# Cyusb3014_-_1.net
KiCad netlist of a schematic drawn in Altium Designer
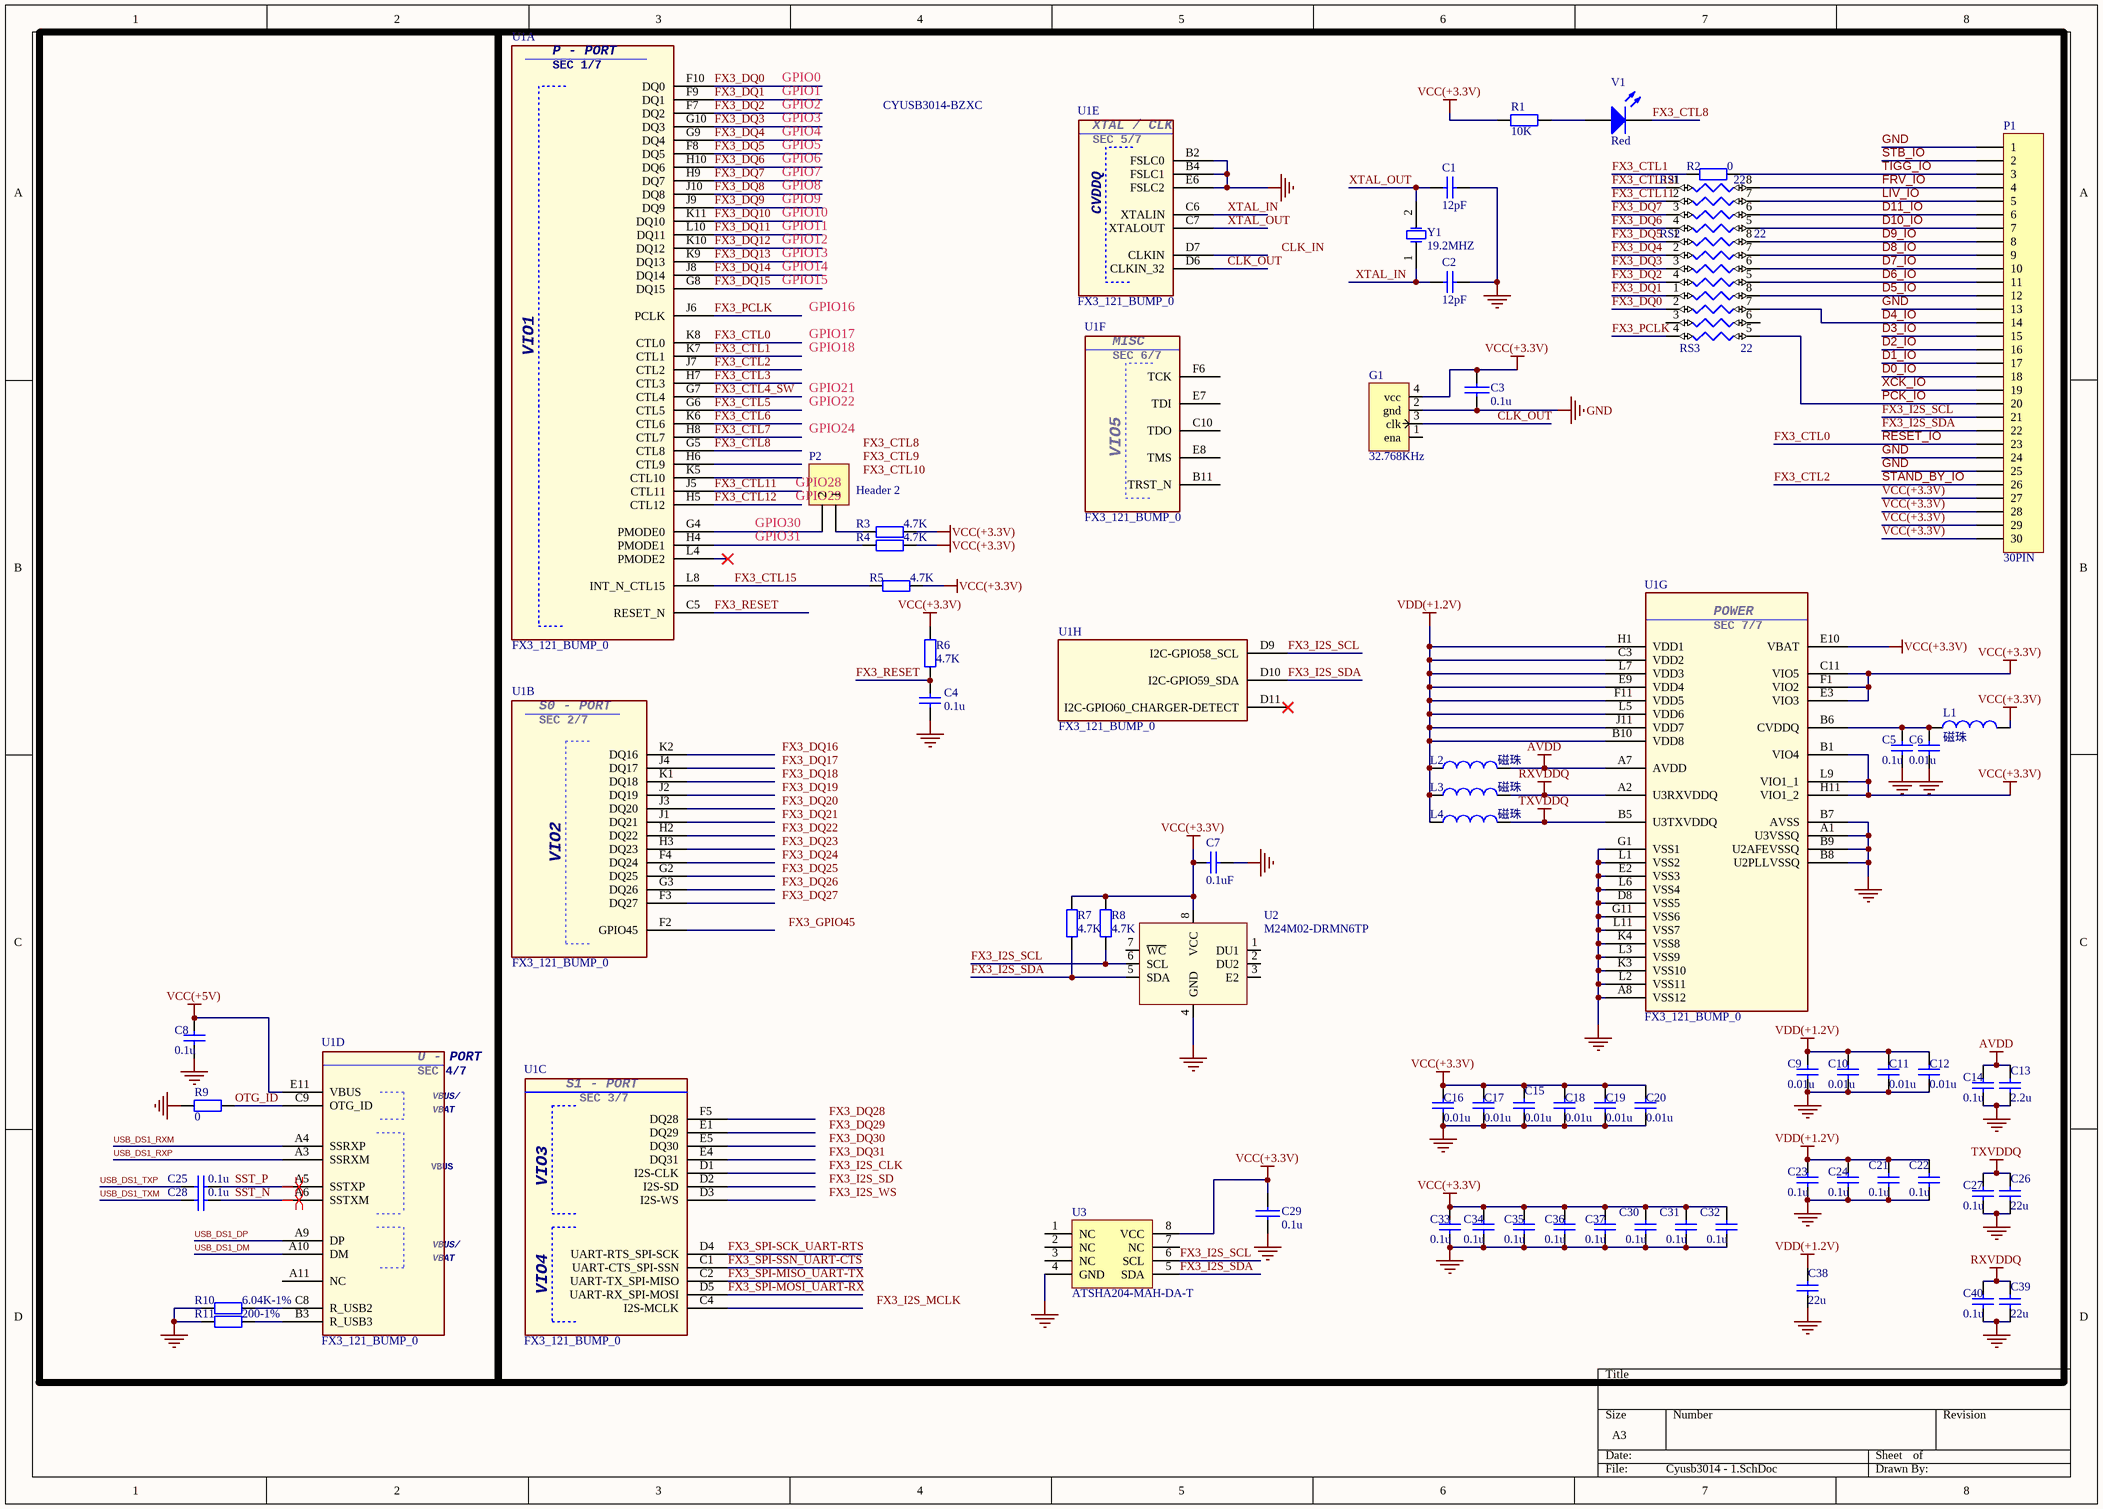
[diagram p0: Cyusb3014 - 1.SchDoc]

(export (version "E")
  (design (tool "Eeschema 10.0.6"))
  (components
    (comp (ref "C1")
      (value "12pF")
      (footprint "0603S-CAP")
      (description "CAP CER SMT 4.3pF 0805")
      (fields
        (field (name "2. MANUFACTURERE PART NUMBER") "C0805C439D5GACTU")
        (field (name "8. ALTERNATE PART") "any")
      )
      (libsource (lib "Peeple_eval") (part "CAP CER SMT 4.3pF 0805"))
    )
    (comp (ref "C2")
      (value "12pF")
      (footprint "0603S-CAP")
      (description "CAP CER SMT 4.3pF 0805")
      (fields
        (field (name "2. MANUFACTURERE PART NUMBER") "C0805C439D5GACTU")
        (field (name "8. ALTERNATE PART") "any")
      )
      (libsource (lib "Peeple_eval") (part "CAP CER SMT 4.3pF 0805"))
    )
    (comp (ref "C3")
      (value "0.1u")
      (footprint "0603S-CAP")
      (description "RC=1206")
      (libsource (lib "*") (part "CAP"))
    )
    (comp (ref "C4")
      (value "0.1u")
      (footprint "0603S-CAP")
      (description "50V/8.2u/0805")
      (fields (field (name "PUBLISHER") "Altium Limited"))
      (libsource (lib "Miscellaneous Devices") (part "Cap"))
    )
    (comp (ref "C5")
      (value "0.1u")
      (footprint "C0402")
      (description "Capacitor")
      (fields (field (name "PUBLISHER") "Altium Limited"))
      (libsource (lib "WM360") (part "CAP0805"))
    )
    (comp (ref "C6")
      (value "0.01u")
      (footprint "C0402")
      (description "Capacitor")
      (fields (field (name "PUBLISHER") "Altium Limited"))
      (libsource (lib "WM360") (part "CAP0805"))
    )
    (comp (ref "C7")
      (value "0.1uF")
      (footprint "0603S-CAP")
      (description "CAP SMT 0.1uF 16V X7R")
      (fields
        (field (name "2. MANUFACTURERE PART NUMBER") "C0805C104K4RACTU")
        (field (name "8. ALTERNATE PART") "any")
      )
      (libsource (lib "Peeple_eval") (part "CAP SMT 0.1uF 16V X7R"))
    )
    (comp (ref "C8")
      (value "0.1u")
      (footprint "C0402")
      (description "Capacitor")
      (fields (field (name "PUBLISHER") "Altium Limited"))
      (libsource (lib "WM360") (part "CAP0805"))
    )
    (comp (ref "C9")
      (value "0.01u")
      (footprint "C0402")
      (description "Capacitor")
      (fields (field (name "PUBLISHER") "Altium Limited"))
      (libsource (lib "WM360") (part "CAP0805"))
    )
    (comp (ref "C10")
      (value "0.01u")
      (footprint "C0402")
      (description "Capacitor")
      (fields (field (name "PUBLISHER") "Altium Limited"))
      (libsource (lib "WM360") (part "CAP0805"))
    )
    (comp (ref "C11")
      (value "0.01u")
      (footprint "C0402")
      (description "Capacitor")
      (fields (field (name "PUBLISHER") "Altium Limited"))
      (libsource (lib "WM360") (part "CAP0805"))
    )
    (comp (ref "C12")
      (value "0.01u")
      (footprint "C0402")
      (description "Capacitor")
      (fields (field (name "PUBLISHER") "Altium Limited"))
      (libsource (lib "WM360") (part "CAP0805"))
    )
    (comp (ref "C13")
      (value "2.2u")
      (footprint "C0805S-CAP")
      (description "Capacitor")
      (fields (field (name "PUBLISHER") "Altium Limited"))
      (libsource (lib "USB_CAMERA") (part "CAP0805"))
    )
    (comp (ref "C14")
      (value "0.1u")
      (footprint "C0402")
      (description "Capacitor")
      (fields (field (name "PUBLISHER") "Altium Limited"))
      (libsource (lib "WM360") (part "CAP0805"))
    )
    (comp (ref "C15")
      (value "0.01u")
      (footprint "C0402")
      (description "Capacitor")
      (fields (field (name "PUBLISHER") "Altium Limited"))
      (libsource (lib "WM360") (part "CAP0805"))
    )
    (comp (ref "C16")
      (value "0.01u")
      (footprint "C0402")
      (description "Capacitor")
      (fields (field (name "PUBLISHER") "Altium Limited"))
      (libsource (lib "WM360") (part "CAP0805"))
    )
    (comp (ref "C17")
      (value "0.01u")
      (footprint "C0402")
      (description "Capacitor")
      (fields (field (name "PUBLISHER") "Altium Limited"))
      (libsource (lib "WM360") (part "CAP0805"))
    )
    (comp (ref "C18")
      (value "0.01u")
      (footprint "C0402")
      (description "Capacitor")
      (fields (field (name "PUBLISHER") "Altium Limited"))
      (libsource (lib "WM360") (part "CAP0805"))
    )
    (comp (ref "C19")
      (value "0.01u")
      (footprint "C0402")
      (description "Capacitor")
      (fields (field (name "PUBLISHER") "Altium Limited"))
      (libsource (lib "WM360") (part "CAP0805"))
    )
    (comp (ref "C20")
      (value "0.01u")
      (footprint "C0402")
      (description "Capacitor")
      (fields (field (name "PUBLISHER") "Altium Limited"))
      (libsource (lib "WM360") (part "CAP0805"))
    )
    (comp (ref "C21")
      (value "0.1u")
      (footprint "C0402")
      (description "Capacitor")
      (fields (field (name "PUBLISHER") "Altium Limited"))
      (libsource (lib "WM360") (part "CAP0805"))
    )
    (comp (ref "C22")
      (value "0.1u")
      (footprint "C0402")
      (description "Capacitor")
      (fields (field (name "PUBLISHER") "Altium Limited"))
      (libsource (lib "WM360") (part "CAP0805"))
    )
    (comp (ref "C23")
      (value "0.1u")
      (footprint "C0402")
      (description "Capacitor")
      (fields (field (name "PUBLISHER") "Altium Limited"))
      (libsource (lib "WM360") (part "CAP0805"))
    )
    (comp (ref "C24")
      (value "0.1u")
      (footprint "C0402")
      (description "Capacitor")
      (fields (field (name "PUBLISHER") "Altium Limited"))
      (libsource (lib "WM360") (part "CAP0805"))
    )
    (comp (ref "C25")
      (value "0.1u")
      (footprint "C0402")
      (description "Capacitor")
      (fields (field (name "PUBLISHER") "Altium Limited"))
      (libsource (lib "WM360") (part "CAP0805"))
    )
    (comp (ref "C26")
      (value "22u")
      (footprint "C0805S-CAP")
      (description "Capacitor")
      (fields (field (name "PUBLISHER") "Altium Limited"))
      (libsource (lib "USB_CAMERA") (part "CAP0805"))
    )
    (comp (ref "C27")
      (value "0.1u")
      (footprint "C0402")
      (description "Capacitor")
      (fields (field (name "PUBLISHER") "Altium Limited"))
      (libsource (lib "WM360") (part "CAP0805"))
    )
    (comp (ref "C28")
      (value "0.1u")
      (footprint "C0402")
      (description "Capacitor")
      (fields (field (name "PUBLISHER") "Altium Limited"))
      (libsource (lib "WM360") (part "CAP0805"))
    )
    (comp (ref "C29")
      (value "0.1u")
      (footprint "0603S-CAP")
      (description "RC=1206")
      (libsource (lib "*") (part "CAP"))
    )
    (comp (ref "C30")
      (value "0.1u")
      (footprint "C0402")
      (description "Capacitor")
      (fields (field (name "PUBLISHER") "Altium Limited"))
      (libsource (lib "WM360") (part "CAP0805"))
    )
    (comp (ref "C31")
      (value "0.1u")
      (footprint "C0402")
      (description "Capacitor")
      (fields (field (name "PUBLISHER") "Altium Limited"))
      (libsource (lib "WM360") (part "CAP0805"))
    )
    (comp (ref "C32")
      (value "0.1u")
      (footprint "C0402")
      (description "Capacitor")
      (fields (field (name "PUBLISHER") "Altium Limited"))
      (libsource (lib "WM360") (part "CAP0805"))
    )
    (comp (ref "C33")
      (value "0.1u")
      (footprint "C0402")
      (description "Capacitor")
      (fields (field (name "PUBLISHER") "Altium Limited"))
      (libsource (lib "WM360") (part "CAP0805"))
    )
    (comp (ref "C34")
      (value "0.1u")
      (footprint "C0402")
      (description "Capacitor")
      (fields (field (name "PUBLISHER") "Altium Limited"))
      (libsource (lib "WM360") (part "CAP0805"))
    )
    (comp (ref "C35")
      (value "0.1u")
      (footprint "C0402")
      (description "Capacitor")
      (fields (field (name "PUBLISHER") "Altium Limited"))
      (libsource (lib "WM360") (part "CAP0805"))
    )
    (comp (ref "C36")
      (value "0.1u")
      (footprint "C0402")
      (description "Capacitor")
      (fields (field (name "PUBLISHER") "Altium Limited"))
      (libsource (lib "WM360") (part "CAP0805"))
    )
    (comp (ref "C37")
      (value "0.1u")
      (footprint "C0402")
      (description "Capacitor")
      (fields (field (name "PUBLISHER") "Altium Limited"))
      (libsource (lib "WM360") (part "CAP0805"))
    )
    (comp (ref "C38")
      (value "22u")
      (footprint "C0805S-CAP")
      (description "Capacitor")
      (fields (field (name "PUBLISHER") "Altium Limited"))
      (libsource (lib "USB_CAMERA") (part "CAP0805"))
    )
    (comp (ref "C39")
      (value "22u")
      (footprint "C0805S-CAP")
      (description "Capacitor")
      (fields (field (name "PUBLISHER") "Altium Limited"))
      (libsource (lib "USB_CAMERA") (part "CAP0805"))
    )
    (comp (ref "C40")
      (value "0.1u")
      (footprint "C0402")
      (description "Capacitor")
      (fields (field (name "PUBLISHER") "Altium Limited"))
      (libsource (lib "WM360") (part "CAP0805"))
    )
    (comp (ref "G1") (value "32.768KHz") (footprint "爱普生晶振3.2×2.5mm") (libsource (lib "*") (part "CTY4-B")))
    (comp (ref "L1")
      (value "磁珠")
      (footprint "L0603")
      (description "Inductor")
      (fields (field (name "PUBLISHER") "Altium Limited"))
      (libsource (lib "Miscellaneous Devices") (part "Inductor"))
    )
    (comp (ref "L2")
      (value "磁珠")
      (footprint "L0603")
      (description "Inductor")
      (fields (field (name "PUBLISHER") "Altium Limited"))
      (libsource (lib "Miscellaneous Devices") (part "Inductor"))
    )
    (comp (ref "L3")
      (value "磁珠")
      (footprint "L0603")
      (description "Inductor")
      (fields (field (name "PUBLISHER") "Altium Limited"))
      (libsource (lib "Miscellaneous Devices") (part "Inductor"))
    )
    (comp (ref "L4")
      (value "磁珠")
      (footprint "L0603")
      (description "Inductor")
      (fields (field (name "PUBLISHER") "Altium Limited"))
      (libsource (lib "Miscellaneous Devices") (part "Inductor"))
    )
    (comp (ref "P1")
      (value "30PIN")
      (footprint "FH12-30S-0.5SH")
      (description "Header, 30-Pin")
      (fields (field (name "PUBLISHER") "Altium Limited"))
      (libsource (lib "Miscellaneous Connectors") (part "Header 30"))
    )
    (comp (ref "P2")
      (value "Header 2")
      (footprint "HDR1X2")
      (description "Header, 2-Pin")
      (fields (field (name "PUBLISHER") "Altium Limited"))
      (libsource (lib "Miscellaneous Connectors") (part "Header 2"))
    )
    (comp (ref "R1")
      (value "10K")
      (footprint "0603S-RES")
      (description "Resistor")
      (fields (field (name "PUBLISHER") "Altium Limited"))
      (libsource (lib "DM642") (part "Res2"))
    )
    (comp (ref "R2")
      (value "0")
      (footprint "0603S-RES")
      (description "Resistor")
      (fields (field (name "PUBLISHER") "Altium Limited"))
      (libsource (lib "DM642") (part "Res2"))
    )
    (comp (ref "R3")
      (value "4.7K")
      (footprint "0603S-RES")
      (description "Resistor")
      (fields (field (name "PUBLISHER") "Altium Limited"))
      (libsource (lib "") (part "Res2_1"))
    )
    (comp (ref "R4")
      (value "4.7K")
      (footprint "0603S-RES")
      (description "Resistor")
      (fields (field (name "PUBLISHER") "Altium Limited"))
      (libsource (lib "") (part "Res2_1"))
    )
    (comp (ref "R5")
      (value "4.7K")
      (footprint "0603S-RES")
      (description "Resistor")
      (fields (field (name "PUBLISHER") "Altium Limited"))
      (libsource (lib "") (part "Res2_3"))
    )
    (comp (ref "R6")
      (value "4.7K")
      (footprint "0603S-RES")
      (description "Resistor")
      (fields (field (name "PUBLISHER") "Altium Limited"))
      (libsource (lib "") (part "Res2_2"))
    )
    (comp (ref "R7")
      (value "4.7K")
      (footprint "0603S-RES")
      (description "Resistor")
      (fields (field (name "PUBLISHER") "Altium Limited"))
      (libsource (lib "") (part "Res2_1"))
    )
    (comp (ref "R8")
      (value "4.7K")
      (footprint "0603S-RES")
      (description "Resistor")
      (fields (field (name "PUBLISHER") "Altium Limited"))
      (libsource (lib "") (part "Res2_1"))
    )
    (comp (ref "R9")
      (value "0")
      (footprint "0603S-RES")
      (description "Resistor")
      (fields (field (name "PUBLISHER") "Altium Limited"))
      (libsource (lib "") (part "Res2_3"))
    )
    (comp (ref "R10")
      (value "6.04K-1%")
      (footprint "0603S-RES")
      (description "Resistor")
      (fields (field (name "PUBLISHER") "Altium Limited"))
      (libsource (lib "") (part "Res2_3"))
    )
    (comp (ref "R11")
      (value "200-1%")
      (footprint "0603S-RES")
      (description "Resistor")
      (fields (field (name "PUBLISHER") "Altium Limited"))
      (libsource (lib "") (part "Res2_3"))
    )
    (comp (ref "RS1") (value "22") (footprint "NC06-4") (libsource (lib "*") (part "RN4")))
    (comp (ref "RS2") (value "22") (footprint "NC06-4") (libsource (lib "*") (part "RN4")))
    (comp (ref "RS3") (value "22") (footprint "NC06-4") (libsource (lib "*") (part "RN4")))
    (comp (ref "U1")
      (value "FX3_121_BUMP_0")
      (footprint "121_BGA_FX3")
      (libsource (lib "USB_CAMERA") (part "FX3_121_BUMP_0"))
    )
    (comp (ref "U2")
      (value "M24M02-DRMN6TP")
      (footprint "SOIC127P600X175-8N")
      (description "IC EEPROM 64KBIT 400KHZ 8SOIC")
      (fields
        (field (name "MANUFACTURER") "Microchip Technology")
        (field (name "MANUFACTURER PART NUMBER") "24LC64-I/SN")
      )
      (libsource (lib "Schlib1") (part "24LC64-I/SN"))
    )
    (comp (ref "U3")
      (value "ATSHA204-MAH-DA-T")
      (footprint "UDFN")
      (libsource (lib "CY7C68013-56") (part "AT24C128"))
    )
    (comp (ref "V1")
      (value "Red")
      (footprint "LED0805S")
      (description "Typical INFRARED GaAs LED")
      (fields (field (name "PUBLISHER") "Altium Limited"))
      (libsource (lib "DM642") (part "LED0"))
    )
    (comp (ref "Y1")
      (value "19.2MHZ")
      (footprint "爱普生晶振3.2×2.5MM - 无源")
      (description "Crystal, CRYSTAL 32.768KHZ 6PF SMD")
      (fields
        (field (name "2. MANUFACTURERE PART NUMBER") "ABS07-120-32.768KHZ-T")
        (field (name "4. SUPPLIER PART NUMBER") "535-11937-1-ND")
      )
      (libsource (lib "Peeple_eval") (part "XTAL 32.768KHZ"))
    )
  )
  (nets
    (net (code "2") (name "/CLK_OUT") (class "Default")
      (node (ref "G1") (pin "3") (pinfunction "clk_3") (pintype "passive"))
      (node (ref "U1") (pin "D6") (pinfunction "CLKIN_32_D6") (pintype "passive"))
    )
    (net (code "3") (name "/D0_IO") (class "Default")
      (node (ref "P1") (pin "18") (pinfunction "18_18") (pintype "passive"))
    )
    (net (code "4") (name "/D1_IO") (class "Default")
      (node (ref "P1") (pin "17") (pinfunction "17_17") (pintype "passive"))
    )
    (net (code "5") (name "/D2_IO") (class "Default")
      (node (ref "P1") (pin "16") (pinfunction "16_16") (pintype "passive"))
    )
    (net (code "6") (name "/D3_IO") (class "Default")
      (node (ref "P1") (pin "15") (pinfunction "15_15") (pintype "passive"))
    )
    (net (code "7") (name "/D4_IO") (class "Default")
      (node (ref "P1") (pin "14") (pinfunction "14_14") (pintype "passive"))
      (node (ref "RS3") (pin "7") (pinfunction "7_7") (pintype "bidirectional"))
    )
    (net (code "8") (name "/D5_IO") (class "Default")
      (node (ref "P1") (pin "12") (pinfunction "12_12") (pintype "passive"))
      (node (ref "RS3") (pin "8") (pinfunction "8_8") (pintype "bidirectional"))
    )
    (net (code "9") (name "/D6_IO") (class "Default")
      (node (ref "P1") (pin "11") (pinfunction "11_11") (pintype "passive"))
      (node (ref "RS2") (pin "5") (pinfunction "5_5") (pintype "bidirectional"))
    )
    (net (code "10") (name "/D7_IO") (class "Default")
      (node (ref "P1") (pin "10") (pinfunction "10_10") (pintype "passive"))
      (node (ref "RS2") (pin "6") (pinfunction "6_6") (pintype "bidirectional"))
    )
    (net (code "11") (name "/D8_IO") (class "Default")
      (node (ref "P1") (pin "9") (pinfunction "9_9") (pintype "passive"))
      (node (ref "RS2") (pin "7") (pinfunction "7_7") (pintype "bidirectional"))
    )
    (net (code "12") (name "/D9_IO") (class "Default")
      (node (ref "P1") (pin "8") (pinfunction "8_8") (pintype "passive"))
      (node (ref "RS2") (pin "8") (pinfunction "8_8") (pintype "bidirectional"))
    )
    (net (code "13") (name "/D10_IO") (class "Default")
      (node (ref "P1") (pin "7") (pinfunction "7_7") (pintype "passive"))
      (node (ref "RS1") (pin "5") (pinfunction "5_5") (pintype "bidirectional"))
    )
    (net (code "14") (name "/D11_IO") (class "Default")
      (node (ref "P1") (pin "6") (pinfunction "6_6") (pintype "passive"))
      (node (ref "RS1") (pin "6") (pinfunction "6_6") (pintype "bidirectional"))
    )
    (net (code "15") (name "/FRV_IO") (class "Default")
      (node (ref "P1") (pin "4") (pinfunction "4_4") (pintype "passive"))
      (node (ref "RS1") (pin "8") (pinfunction "8_8") (pintype "bidirectional"))
    )
    (net (code "16") (name "/FX3_CTL0") (class "Default")
      (node (ref "P1") (pin "23") (pinfunction "23_23") (pintype "passive"))
      (node (ref "U1") (pin "K8") (pinfunction "CTL0_K8") (pintype "passive"))
    )
    (net (code "17") (name "/FX3_CTL1") (class "Default")
      (node (ref "R2") (pin "2") (pinfunction "2_2") (pintype "passive"))
      (node (ref "U1") (pin "K7") (pinfunction "CTL1_K7") (pintype "passive"))
    )
    (net (code "18") (name "/FX3_CTL2") (class "Default")
      (node (ref "P1") (pin "26") (pinfunction "26_26") (pintype "passive"))
      (node (ref "U1") (pin "J7") (pinfunction "CTL2_J7") (pintype "passive"))
    )
    (net (code "19") (name "/FX3_CTL3") (class "Default")
      (node (ref "U1") (pin "H7") (pinfunction "CTL3_H7") (pintype "passive"))
    )
    (net (code "20") (name "/FX3_CTL4_SW") (class "Default")
      (node (ref "U1") (pin "G7") (pinfunction "CTL4_G7") (pintype "passive"))
    )
    (net (code "21") (name "/FX3_CTL5") (class "Default")
      (node (ref "U1") (pin "G6") (pinfunction "CTL5_G6") (pintype "passive"))
    )
    (net (code "22") (name "/FX3_CTL6") (class "Default")
      (node (ref "U1") (pin "K6") (pinfunction "CTL6_K6") (pintype "passive"))
    )
    (net (code "23") (name "/FX3_CTL7") (class "Default")
      (node (ref "U1") (pin "H8") (pinfunction "CTL7_H8") (pintype "passive"))
    )
    (net (code "24") (name "/FX3_CTL8") (class "Default")
      (node (ref "U1") (pin "G5") (pinfunction "CTL8_G5") (pintype "passive"))
      (node (ref "V1") (pin "2") (pinfunction "K_2") (pintype "passive"))
    )
    (net (code "27") (name "/FX3_CTL11") (class "Default")
      (node (ref "RS1") (pin "2") (pinfunction "2_2") (pintype "bidirectional"))
      (node (ref "U1") (pin "J5") (pinfunction "CTL11_J5") (pintype "passive"))
    )
    (net (code "28") (name "/FX3_CTL12") (class "Default")
      (node (ref "RS1") (pin "1") (pinfunction "1_1") (pintype "bidirectional"))
      (node (ref "U1") (pin "H5") (pinfunction "CTL12_H5") (pintype "passive"))
    )
    (net (code "29") (name "/FX3_CTL15") (class "Default")
      (node (ref "R5") (pin "2") (pinfunction "2_2") (pintype "passive"))
      (node (ref "U1") (pin "L8") (pinfunction "INT_N_CTL15_L8") (pintype "passive"))
    )
    (net (code "30") (name "/FX3_DQ0") (class "Default")
      (node (ref "RS3") (pin "2") (pinfunction "2_2") (pintype "bidirectional"))
      (node (ref "U1") (pin "F10") (pinfunction "DQ0_F10") (pintype "passive"))
    )
    (net (code "31") (name "/FX3_DQ1") (class "Default")
      (node (ref "RS3") (pin "1") (pinfunction "1_1") (pintype "bidirectional"))
      (node (ref "U1") (pin "F9") (pinfunction "DQ1_F9") (pintype "passive"))
    )
    (net (code "32") (name "/FX3_DQ2") (class "Default")
      (node (ref "RS2") (pin "4") (pinfunction "4_4") (pintype "bidirectional"))
      (node (ref "U1") (pin "F7") (pinfunction "DQ2_F7") (pintype "passive"))
    )
    (net (code "33") (name "/FX3_DQ3") (class "Default")
      (node (ref "RS2") (pin "3") (pinfunction "3_3") (pintype "bidirectional"))
      (node (ref "U1") (pin "G10") (pinfunction "DQ3_G10") (pintype "passive"))
    )
    (net (code "34") (name "/FX3_DQ4") (class "Default")
      (node (ref "RS2") (pin "2") (pinfunction "2_2") (pintype "bidirectional"))
      (node (ref "U1") (pin "G9") (pinfunction "DQ4_G9") (pintype "passive"))
    )
    (net (code "35") (name "/FX3_DQ5") (class "Default")
      (node (ref "RS2") (pin "1") (pinfunction "1_1") (pintype "bidirectional"))
      (node (ref "U1") (pin "F8") (pinfunction "DQ5_F8") (pintype "passive"))
    )
    (net (code "36") (name "/FX3_DQ6") (class "Default")
      (node (ref "RS1") (pin "4") (pinfunction "4_4") (pintype "bidirectional"))
      (node (ref "U1") (pin "H10") (pinfunction "DQ6_H10") (pintype "passive"))
    )
    (net (code "37") (name "/FX3_DQ7") (class "Default")
      (node (ref "RS1") (pin "3") (pinfunction "3_3") (pintype "bidirectional"))
      (node (ref "U1") (pin "H9") (pinfunction "DQ7_H9") (pintype "passive"))
    )
    (net (code "38") (name "/FX3_DQ8") (class "Default")
      (node (ref "U1") (pin "J10") (pinfunction "DQ8_J10") (pintype "passive"))
    )
    (net (code "39") (name "/FX3_DQ9") (class "Default")
      (node (ref "U1") (pin "J9") (pinfunction "DQ9_J9") (pintype "passive"))
    )
    (net (code "40") (name "/FX3_DQ10") (class "Default")
      (node (ref "U1") (pin "K11") (pinfunction "DQ10_K11") (pintype "passive"))
    )
    (net (code "41") (name "/FX3_DQ11") (class "Default")
      (node (ref "U1") (pin "L10") (pinfunction "DQ11_L10") (pintype "passive"))
    )
    (net (code "42") (name "/FX3_DQ12") (class "Default")
      (node (ref "U1") (pin "K10") (pinfunction "DQ12_K10") (pintype "passive"))
    )
    (net (code "43") (name "/FX3_DQ13") (class "Default")
      (node (ref "U1") (pin "K9") (pinfunction "DQ13_K9") (pintype "passive"))
    )
    (net (code "44") (name "/FX3_DQ14") (class "Default")
      (node (ref "U1") (pin "J8") (pinfunction "DQ14_J8") (pintype "passive"))
    )
    (net (code "45") (name "/FX3_DQ15") (class "Default")
      (node (ref "U1") (pin "G8") (pinfunction "DQ15_G8") (pintype "passive"))
    )
    (net (code "65") (name "/FX3_I2S_SCL") (class "Default")
      (node (ref "P1") (pin "21") (pinfunction "21_21") (pintype "passive"))
      (node (ref "R8") (pin "1") (pinfunction "1_1") (pintype "passive"))
      (node (ref "U1") (pin "D9") (pinfunction "I2C-GPIO58_SCL_D9") (pintype "passive"))
      (node (ref "U2") (pin "6") (pinfunction "SCL_6") (pintype "passive"))
      (node (ref "U3") (pin "6") (pinfunction "SCL_6") (pintype "passive"))
    )
    (net (code "67") (name "/FX3_I2S_SDA") (class "Default")
      (node (ref "P1") (pin "22") (pinfunction "22_22") (pintype "passive"))
      (node (ref "R7") (pin "1") (pinfunction "1_1") (pintype "passive"))
      (node (ref "U1") (pin "D10") (pinfunction "I2C-GPIO59_SDA_D10") (pintype "passive"))
      (node (ref "U2") (pin "5") (pinfunction "SDA_5") (pintype "passive"))
      (node (ref "U3") (pin "5") (pinfunction "SDA_5") (pintype "passive"))
    )
    (net (code "69") (name "/FX3_PCLK") (class "Default")
      (node (ref "RS3") (pin "4") (pinfunction "4_4") (pintype "bidirectional"))
      (node (ref "U1") (pin "J6") (pinfunction "PCLK_J6") (pintype "passive"))
    )
    (net (code "70") (name "/FX3_RESET") (class "Default")
      (node (ref "C4") (pin "2") (pinfunction "2_2") (pintype "passive"))
      (node (ref "R6") (pin "2") (pinfunction "2_2") (pintype "passive"))
      (node (ref "U1") (pin "C5") (pinfunction "RESET_N_C5") (pintype "passive"))
    )
    (net (code "71") (name "/FX3_SPI-MISO_UART-TX") (class "Default")
      (node (ref "U1") (pin "C2") (pinfunction "UART-TX_SPI-MISO_C2") (pintype "passive"))
    )
    (net (code "72") (name "/FX3_SPI-MOSI_UART-RX") (class "Default")
      (node (ref "U1") (pin "D5") (pinfunction "UART-RX_SPI-MOSI_D5") (pintype "passive"))
    )
    (net (code "73") (name "/FX3_SPI-SCK_UART-RTS") (class "Default")
      (node (ref "U1") (pin "D4") (pinfunction "UART-RTS_SPI-SCK_D4") (pintype "passive"))
    )
    (net (code "74") (name "/FX3_SPI-SSN_UART-CTS") (class "Default")
      (node (ref "U1") (pin "C1") (pinfunction "UART-CTS_SPI-SSN_C1") (pintype "passive"))
    )
    (net (code "75") (name "/LIV_IO") (class "Default")
      (node (ref "P1") (pin "5") (pinfunction "5_5") (pintype "passive"))
      (node (ref "RS1") (pin "7") (pinfunction "7_7") (pintype "bidirectional"))
    )
    (net (code "76") (name "/OTG_ID") (class "Default")
      (node (ref "R9") (pin "1") (pinfunction "1_1") (pintype "passive"))
      (node (ref "U1") (pin "C9") (pinfunction "OTG_ID_C9") (pintype "passive"))
    )
    (net (code "77") (name "/PCK_IO") (class "Default")
      (node (ref "P1") (pin "20") (pinfunction "20_20") (pintype "passive"))
      (node (ref "RS3") (pin "5") (pinfunction "5_5") (pintype "bidirectional"))
    )
    (net (code "78") (name "/SST_N") (class "Default")
      (node (ref "C28") (pin "2") (pinfunction "2_2") (pintype "passive"))
      (node (ref "U1") (pin "A6") (pinfunction "SSTXM_A6") (pintype "passive"))
    )
    (net (code "79") (name "/SST_P") (class "Default")
      (node (ref "C25") (pin "2") (pinfunction "2_2") (pintype "passive"))
      (node (ref "U1") (pin "A5") (pinfunction "SSTXP_A5") (pintype "passive"))
    )
    (net (code "80") (name "/STB_IO") (class "Default")
      (node (ref "P1") (pin "2") (pinfunction "2_2") (pintype "passive"))
    )
    (net (code "81") (name "/TIGG_IO") (class "Default")
      (node (ref "P1") (pin "3") (pinfunction "3_3") (pintype "passive"))
      (node (ref "R2") (pin "1") (pinfunction "1_1") (pintype "passive"))
    )
    (net (code "82") (name "/USB_DS1_DM") (class "Default")
      (node (ref "U1") (pin "A10") (pinfunction "DM_A10") (pintype "passive"))
    )
    (net (code "83") (name "/USB_DS1_DP") (class "Default")
      (node (ref "U1") (pin "A9") (pinfunction "DP_A9") (pintype "passive"))
    )
    (net (code "84") (name "/USB_DS1_RXM") (class "Default")
      (node (ref "U1") (pin "A4") (pinfunction "SSRXP_A4") (pintype "passive"))
    )
    (net (code "85") (name "/USB_DS1_RXP") (class "Default")
      (node (ref "U1") (pin "A3") (pinfunction "SSRXM_A3") (pintype "passive"))
    )
    (net (code "86") (name "/USB_DS1_TXM") (class "Default")
      (node (ref "C28") (pin "1") (pinfunction "1_1") (pintype "passive"))
    )
    (net (code "87") (name "/USB_DS1_TXP") (class "Default")
      (node (ref "C25") (pin "1") (pinfunction "1_1") (pintype "passive"))
    )
    (net (code "88") (name "/XCK_IO") (class "Default")
      (node (ref "P1") (pin "19") (pinfunction "19_19") (pintype "passive"))
    )
    (net (code "89") (name "/XTAL_IN") (class "Default")
      (node (ref "C2") (pin "2") (pinfunction "2_2") (pintype "passive"))
      (node (ref "U1") (pin "C6") (pinfunction "XTALIN_C6") (pintype "passive"))
      (node (ref "Y1") (pin "1") (pinfunction "OSC1_1") (pintype "passive"))
    )
    (net (code "90") (name "/XTAL_OUT") (class "Default")
      (node (ref "C1") (pin "2") (pinfunction "2_2") (pintype "passive"))
      (node (ref "U1") (pin "C7") (pinfunction "XTALOUT_C7") (pintype "passive"))
      (node (ref "Y1") (pin "2") (pinfunction "OSC2_2") (pintype "passive"))
    )
    (net (code "91") (name "AVDD") (class "Default")
      (node (ref "C13") (pin "2") (pinfunction "2_2") (pintype "passive"))
      (node (ref "C14") (pin "1") (pinfunction "1_1") (pintype "passive"))
      (node (ref "L2") (pin "2") (pinfunction "2_2") (pintype "passive"))
      (node (ref "U1") (pin "A7") (pinfunction "AVDD_A7") (pintype "passive"))
    )
    (net (code "92") (name "GND") (class "Default")
      (node (ref "C1") (pin "1") (pinfunction "1_1") (pintype "passive"))
      (node (ref "C10") (pin "2") (pinfunction "2_2") (pintype "passive"))
      (node (ref "C11") (pin "2") (pinfunction "2_2") (pintype "passive"))
      (node (ref "C12") (pin "2") (pinfunction "2_2") (pintype "passive"))
      (node (ref "C13") (pin "1") (pinfunction "1_1") (pintype "passive"))
      (node (ref "C14") (pin "2") (pinfunction "2_2") (pintype "passive"))
      (node (ref "C15") (pin "2") (pinfunction "2_2") (pintype "passive"))
      (node (ref "C16") (pin "2") (pinfunction "2_2") (pintype "passive"))
      (node (ref "C17") (pin "2") (pinfunction "2_2") (pintype "passive"))
      (node (ref "C18") (pin "2") (pinfunction "2_2") (pintype "passive"))
      (node (ref "C19") (pin "2") (pinfunction "2_2") (pintype "passive"))
      (node (ref "C2") (pin "1") (pinfunction "1_1") (pintype "passive"))
      (node (ref "C20") (pin "2") (pinfunction "2_2") (pintype "passive"))
      (node (ref "C21") (pin "2") (pinfunction "2_2") (pintype "passive"))
      (node (ref "C22") (pin "2") (pinfunction "2_2") (pintype "passive"))
      (node (ref "C23") (pin "2") (pinfunction "2_2") (pintype "passive"))
      (node (ref "C24") (pin "2") (pinfunction "2_2") (pintype "passive"))
      (node (ref "C26") (pin "1") (pinfunction "1_1") (pintype "passive"))
      (node (ref "C27") (pin "2") (pinfunction "2_2") (pintype "passive"))
      (node (ref "C29") (pin "2") (pintype "passive"))
      (node (ref "C3") (pin "2") (pintype "passive"))
      (node (ref "C30") (pin "2") (pinfunction "2_2") (pintype "passive"))
      (node (ref "C31") (pin "2") (pinfunction "2_2") (pintype "passive"))
      (node (ref "C32") (pin "2") (pinfunction "2_2") (pintype "passive"))
      (node (ref "C33") (pin "2") (pinfunction "2_2") (pintype "passive"))
      (node (ref "C34") (pin "2") (pinfunction "2_2") (pintype "passive"))
      (node (ref "C35") (pin "2") (pinfunction "2_2") (pintype "passive"))
      (node (ref "C36") (pin "2") (pinfunction "2_2") (pintype "passive"))
      (node (ref "C37") (pin "2") (pinfunction "2_2") (pintype "passive"))
      (node (ref "C38") (pin "1") (pinfunction "1_1") (pintype "passive"))
      (node (ref "C39") (pin "1") (pinfunction "1_1") (pintype "passive"))
      (node (ref "C4") (pin "1") (pinfunction "1_1") (pintype "passive"))
      (node (ref "C40") (pin "2") (pinfunction "2_2") (pintype "passive"))
      (node (ref "C5") (pin "2") (pinfunction "2_2") (pintype "passive"))
      (node (ref "C6") (pin "2") (pinfunction "2_2") (pintype "passive"))
      (node (ref "C7") (pin "1") (pinfunction "1_1") (pintype "passive"))
      (node (ref "C8") (pin "2") (pinfunction "2_2") (pintype "passive"))
      (node (ref "C9") (pin "2") (pinfunction "2_2") (pintype "passive"))
      (node (ref "G1") (pin "2") (pinfunction "gnd_2") (pintype "power_in"))
      (node (ref "P1") (pin "1") (pinfunction "1_1") (pintype "passive"))
      (node (ref "P1") (pin "13") (pinfunction "13_13") (pintype "passive"))
      (node (ref "P1") (pin "24") (pinfunction "24_24") (pintype "passive"))
      (node (ref "P1") (pin "25") (pinfunction "25_25") (pintype "passive"))
      (node (ref "R10") (pin "2") (pinfunction "2_2") (pintype "passive"))
      (node (ref "R11") (pin "2") (pinfunction "2_2") (pintype "passive"))
      (node (ref "R9") (pin "2") (pinfunction "2_2") (pintype "passive"))
      (node (ref "U1") (pin "A1") (pinfunction "U3VSSQ_A1") (pintype "passive"))
      (node (ref "U1") (pin "A8") (pinfunction "VSS12_A8") (pintype "passive"))
      (node (ref "U1") (pin "B2") (pinfunction "FSLC0_B2") (pintype "passive"))
      (node (ref "U1") (pin "B4") (pinfunction "FSLC1_B4") (pintype "passive"))
      (node (ref "U1") (pin "B7") (pinfunction "AVSS_B7") (pintype "passive"))
      (node (ref "U1") (pin "B8") (pinfunction "U2PLLVSSQ_B8") (pintype "passive"))
      (node (ref "U1") (pin "B9") (pinfunction "U2AFEVSSQ_B9") (pintype "passive"))
      (node (ref "U1") (pin "D8") (pinfunction "VSS5_D8") (pintype "passive"))
      (node (ref "U1") (pin "E2") (pinfunction "VSS3_E2") (pintype "passive"))
      (node (ref "U1") (pin "E6") (pinfunction "FSLC2_E6") (pintype "passive"))
      (node (ref "U1") (pin "G1") (pinfunction "VSS1_G1") (pintype "passive"))
      (node (ref "U1") (pin "G11") (pinfunction "VSS6_G11") (pintype "passive"))
      (node (ref "U1") (pin "K3") (pinfunction "VSS10_K3") (pintype "passive"))
      (node (ref "U1") (pin "K4") (pinfunction "VSS8_K4") (pintype "passive"))
      (node (ref "U1") (pin "L1") (pinfunction "VSS2_L1") (pintype "passive"))
      (node (ref "U1") (pin "L11") (pinfunction "VSS7_L11") (pintype "passive"))
      (node (ref "U1") (pin "L2") (pinfunction "VSS11_L2") (pintype "passive"))
      (node (ref "U1") (pin "L3") (pinfunction "VSS9_L3") (pintype "passive"))
      (node (ref "U1") (pin "L6") (pinfunction "VSS4_L6") (pintype "passive"))
      (node (ref "U2") (pin "4") (pinfunction "GND_4") (pintype "passive"))
      (node (ref "U3") (pin "4") (pinfunction "GND_4") (pintype "passive"))
    )
    (net (code "93") (name "Net-(P2-Pad1)") (class "Default")
      (node (ref "P2") (pin "1") (pinfunction "1_1") (pintype "passive"))
      (node (ref "R3") (pin "1") (pinfunction "1_1") (pintype "passive"))
    )
    (net (code "94") (name "Net-(U1A-PMODE0)") (class "Default")
      (node (ref "P2") (pin "2") (pinfunction "2_2") (pintype "passive"))
      (node (ref "U1") (pin "G4") (pinfunction "PMODE0_G4") (pintype "passive"))
    )
    (net (code "95") (name "Net-(U1A-PMODE1)") (class "Default")
      (node (ref "R4") (pin "1") (pinfunction "1_1") (pintype "passive"))
      (node (ref "U1") (pin "H4") (pinfunction "PMODE1_H4") (pintype "passive"))
    )
    (net (code "96") (name "Net-(U1D-R_USB2)") (class "Default")
      (node (ref "R10") (pin "1") (pinfunction "1_1") (pintype "passive"))
      (node (ref "U1") (pin "C8") (pinfunction "R_USB2_C8") (pintype "passive"))
    )
    (net (code "97") (name "Net-(U1D-R_USB3)") (class "Default")
      (node (ref "R11") (pin "1") (pinfunction "1_1") (pintype "passive"))
      (node (ref "U1") (pin "B3") (pinfunction "R_USB3_B3") (pintype "passive"))
    )
    (net (code "98") (name "Net-(U1G-CVDDQ)") (class "Default")
      (node (ref "C5") (pin "1") (pinfunction "1_1") (pintype "passive"))
      (node (ref "C6") (pin "1") (pinfunction "1_1") (pintype "passive"))
      (node (ref "L1") (pin "1") (pinfunction "1_1") (pintype "passive"))
      (node (ref "U1") (pin "B6") (pinfunction "CVDDQ_B6") (pintype "passive"))
    )
    (net (code "99") (name "Net-(V1-A)") (class "Default")
      (node (ref "R1") (pin "1") (pinfunction "1_1") (pintype "passive"))
      (node (ref "V1") (pin "1") (pinfunction "A_1") (pintype "passive"))
    )
    (net (code "100") (name "RXVDDQ") (class "Default")
      (node (ref "C39") (pin "2") (pinfunction "2_2") (pintype "passive"))
      (node (ref "C40") (pin "1") (pinfunction "1_1") (pintype "passive"))
      (node (ref "L3") (pin "2") (pinfunction "2_2") (pintype "passive"))
      (node (ref "U1") (pin "A2") (pinfunction "U3RXVDDQ_A2") (pintype "passive"))
    )
    (net (code "101") (name "TXVDDQ") (class "Default")
      (node (ref "C26") (pin "2") (pinfunction "2_2") (pintype "passive"))
      (node (ref "C27") (pin "1") (pinfunction "1_1") (pintype "passive"))
      (node (ref "L4") (pin "2") (pinfunction "2_2") (pintype "passive"))
      (node (ref "U1") (pin "B5") (pinfunction "U3TXVDDQ_B5") (pintype "passive"))
    )
    (net (code "102") (name "VCC(+3.3V)") (class "Default")
      (node (ref "C15") (pin "1") (pinfunction "1_1") (pintype "passive"))
      (node (ref "C16") (pin "1") (pinfunction "1_1") (pintype "passive"))
      (node (ref "C17") (pin "1") (pinfunction "1_1") (pintype "passive"))
      (node (ref "C18") (pin "1") (pinfunction "1_1") (pintype "passive"))
      (node (ref "C19") (pin "1") (pinfunction "1_1") (pintype "passive"))
      (node (ref "C20") (pin "1") (pinfunction "1_1") (pintype "passive"))
      (node (ref "C29") (pin "1") (pintype "passive"))
      (node (ref "C3") (pin "1") (pintype "passive"))
      (node (ref "C30") (pin "1") (pinfunction "1_1") (pintype "passive"))
      (node (ref "C31") (pin "1") (pinfunction "1_1") (pintype "passive"))
      (node (ref "C32") (pin "1") (pinfunction "1_1") (pintype "passive"))
      (node (ref "C33") (pin "1") (pinfunction "1_1") (pintype "passive"))
      (node (ref "C34") (pin "1") (pinfunction "1_1") (pintype "passive"))
      (node (ref "C35") (pin "1") (pinfunction "1_1") (pintype "passive"))
      (node (ref "C36") (pin "1") (pinfunction "1_1") (pintype "passive"))
      (node (ref "C37") (pin "1") (pinfunction "1_1") (pintype "passive"))
      (node (ref "C7") (pin "2") (pinfunction "2_2") (pintype "passive"))
      (node (ref "G1") (pin "4") (pinfunction "vcc_4") (pintype "power_in"))
      (node (ref "L1") (pin "2") (pinfunction "2_2") (pintype "passive"))
      (node (ref "P1") (pin "27") (pinfunction "27_27") (pintype "passive"))
      (node (ref "P1") (pin "28") (pinfunction "28_28") (pintype "passive"))
      (node (ref "P1") (pin "29") (pinfunction "29_29") (pintype "passive"))
      (node (ref "P1") (pin "30") (pinfunction "30_30") (pintype "passive"))
      (node (ref "R1") (pin "2") (pinfunction "2_2") (pintype "passive"))
      (node (ref "R3") (pin "2") (pinfunction "2_2") (pintype "passive"))
      (node (ref "R4") (pin "2") (pinfunction "2_2") (pintype "passive"))
      (node (ref "R5") (pin "1") (pinfunction "1_1") (pintype "passive"))
      (node (ref "R6") (pin "1") (pinfunction "1_1") (pintype "passive"))
      (node (ref "R7") (pin "2") (pinfunction "2_2") (pintype "passive"))
      (node (ref "R8") (pin "2") (pinfunction "2_2") (pintype "passive"))
      (node (ref "U1") (pin "B1") (pinfunction "VIO4_B1") (pintype "passive"))
      (node (ref "U1") (pin "C11") (pinfunction "VIO5_C11") (pintype "passive"))
      (node (ref "U1") (pin "E10") (pinfunction "VBAT_E10") (pintype "passive"))
      (node (ref "U1") (pin "E3") (pinfunction "VIO3_E3") (pintype "passive"))
      (node (ref "U1") (pin "F1") (pinfunction "VIO2_F1") (pintype "passive"))
      (node (ref "U1") (pin "H11") (pinfunction "VIO1_2_H11") (pintype "passive"))
      (node (ref "U1") (pin "L9") (pinfunction "VIO1_1_L9") (pintype "passive"))
      (node (ref "U2") (pin "8") (pinfunction "VCC_8") (pintype "passive"))
      (node (ref "U3") (pin "8") (pinfunction "VCC_8") (pintype "passive"))
    )
    (net (code "103") (name "VCC(+5V)") (class "Default")
      (node (ref "C8") (pin "1") (pinfunction "1_1") (pintype "passive"))
      (node (ref "U1") (pin "E11") (pinfunction "VBUS_E11") (pintype "passive"))
    )
    (net (code "104") (name "VDD(+1.2V)") (class "Default")
      (node (ref "C10") (pin "1") (pinfunction "1_1") (pintype "passive"))
      (node (ref "C11") (pin "1") (pinfunction "1_1") (pintype "passive"))
      (node (ref "C12") (pin "1") (pinfunction "1_1") (pintype "passive"))
      (node (ref "C21") (pin "1") (pinfunction "1_1") (pintype "passive"))
      (node (ref "C22") (pin "1") (pinfunction "1_1") (pintype "passive"))
      (node (ref "C23") (pin "1") (pinfunction "1_1") (pintype "passive"))
      (node (ref "C24") (pin "1") (pinfunction "1_1") (pintype "passive"))
      (node (ref "C38") (pin "2") (pinfunction "2_2") (pintype "passive"))
      (node (ref "C9") (pin "1") (pinfunction "1_1") (pintype "passive"))
      (node (ref "L2") (pin "1") (pinfunction "1_1") (pintype "passive"))
      (node (ref "L3") (pin "1") (pinfunction "1_1") (pintype "passive"))
      (node (ref "L4") (pin "1") (pinfunction "1_1") (pintype "passive"))
      (node (ref "U1") (pin "B10") (pinfunction "VDD8_B10") (pintype "passive"))
      (node (ref "U1") (pin "C3") (pinfunction "VDD2_C3") (pintype "passive"))
      (node (ref "U1") (pin "E9") (pinfunction "VDD4_E9") (pintype "passive"))
      (node (ref "U1") (pin "F11") (pinfunction "VDD5_F11") (pintype "passive"))
      (node (ref "U1") (pin "H1") (pinfunction "VDD1_H1") (pintype "passive"))
      (node (ref "U1") (pin "J11") (pinfunction "VDD7_J11") (pintype "passive"))
      (node (ref "U1") (pin "L5") (pinfunction "VDD6_L5") (pintype "passive"))
      (node (ref "U1") (pin "L7") (pinfunction "VDD3_L7") (pintype "passive"))
    )
    (net (code "105") (name "unconnected-(G1-ena-Pad1)") (class "Default")
      (node (ref "G1") (pin "1") (pinfunction "ena_1") (pintype "passive"))
    )
    (net (code "106") (name "unconnected-(RS3-Pad3)") (class "Default")
      (node (ref "RS3") (pin "3") (pinfunction "3_3") (pintype "bidirectional"))
    )
    (net (code "107") (name "unconnected-(RS3-Pad6)") (class "Default")
      (node (ref "RS3") (pin "6") (pinfunction "6_6") (pintype "bidirectional"))
    )
    (net (code "108") (name "unconnected-(U1A-CTL9-PadH6)") (class "Default")
      (node (ref "U1") (pin "H6") (pinfunction "CTL9_H6") (pintype "passive"))
    )
    (net (code "109") (name "unconnected-(U1A-CTL10-PadK5)") (class "Default")
      (node (ref "U1") (pin "K5") (pinfunction "CTL10_K5") (pintype "passive"))
    )
    (net (code "110") (name "unconnected-(U1A-PMODE2-PadL4)") (class "Default")
      (node (ref "U1") (pin "L4") (pinfunction "PMODE2_L4") (pintype "passive+no_connect"))
    )
    (net (code "111") (name "unconnected-(U1B-DQ16-PadK2)") (class "Default")
      (node (ref "U1") (pin "K2") (pinfunction "DQ16_K2") (pintype "passive"))
    )
    (net (code "112") (name "unconnected-(U1B-DQ17-PadJ4)") (class "Default")
      (node (ref "U1") (pin "J4") (pinfunction "DQ17_J4") (pintype "passive"))
    )
    (net (code "113") (name "unconnected-(U1B-DQ18-PadK1)") (class "Default")
      (node (ref "U1") (pin "K1") (pinfunction "DQ18_K1") (pintype "passive"))
    )
    (net (code "114") (name "unconnected-(U1B-DQ19-PadJ2)") (class "Default")
      (node (ref "U1") (pin "J2") (pinfunction "DQ19_J2") (pintype "passive"))
    )
    (net (code "115") (name "unconnected-(U1B-DQ20-PadJ3)") (class "Default")
      (node (ref "U1") (pin "J3") (pinfunction "DQ20_J3") (pintype "passive"))
    )
    (net (code "116") (name "unconnected-(U1B-DQ21-PadJ1)") (class "Default")
      (node (ref "U1") (pin "J1") (pinfunction "DQ21_J1") (pintype "passive"))
    )
    (net (code "117") (name "unconnected-(U1B-DQ22-PadH2)") (class "Default")
      (node (ref "U1") (pin "H2") (pinfunction "DQ22_H2") (pintype "passive"))
    )
    (net (code "118") (name "unconnected-(U1B-DQ23-PadH3)") (class "Default")
      (node (ref "U1") (pin "H3") (pinfunction "DQ23_H3") (pintype "passive"))
    )
    (net (code "119") (name "unconnected-(U1B-DQ24-PadF4)") (class "Default")
      (node (ref "U1") (pin "F4") (pinfunction "DQ24_F4") (pintype "passive"))
    )
    (net (code "120") (name "unconnected-(U1B-DQ25-PadG2)") (class "Default")
      (node (ref "U1") (pin "G2") (pinfunction "DQ25_G2") (pintype "passive"))
    )
    (net (code "121") (name "unconnected-(U1B-DQ26-PadG3)") (class "Default")
      (node (ref "U1") (pin "G3") (pinfunction "DQ26_G3") (pintype "passive"))
    )
    (net (code "122") (name "unconnected-(U1B-DQ27-PadF3)") (class "Default")
      (node (ref "U1") (pin "F3") (pinfunction "DQ27_F3") (pintype "passive"))
    )
    (net (code "123") (name "unconnected-(U1B-GPIO45-PadF2)") (class "Default")
      (node (ref "U1") (pin "F2") (pinfunction "GPIO45_F2") (pintype "passive"))
    )
    (net (code "124") (name "unconnected-(U1C-DQ28-PadF5)") (class "Default")
      (node (ref "U1") (pin "F5") (pinfunction "DQ28_F5") (pintype "passive"))
    )
    (net (code "125") (name "unconnected-(U1C-DQ29-PadE1)") (class "Default")
      (node (ref "U1") (pin "E1") (pinfunction "DQ29_E1") (pintype "passive"))
    )
    (net (code "126") (name "unconnected-(U1C-DQ30-PadE5)") (class "Default")
      (node (ref "U1") (pin "E5") (pinfunction "DQ30_E5") (pintype "passive"))
    )
    (net (code "127") (name "unconnected-(U1C-DQ31-PadE4)") (class "Default")
      (node (ref "U1") (pin "E4") (pinfunction "DQ31_E4") (pintype "passive"))
    )
    (net (code "128") (name "unconnected-(U1C-I2S-CLK-PadD1)") (class "Default")
      (node (ref "U1") (pin "D1") (pinfunction "I2S-CLK_D1") (pintype "passive"))
    )
    (net (code "129") (name "unconnected-(U1C-I2S-MCLK-PadC4)") (class "Default")
      (node (ref "U1") (pin "C4") (pinfunction "I2S-MCLK_C4") (pintype "passive"))
    )
    (net (code "130") (name "unconnected-(U1C-I2S-SD-PadD2)") (class "Default")
      (node (ref "U1") (pin "D2") (pinfunction "I2S-SD_D2") (pintype "passive"))
    )
    (net (code "131") (name "unconnected-(U1C-I2S-WS-PadD3)") (class "Default")
      (node (ref "U1") (pin "D3") (pinfunction "I2S-WS_D3") (pintype "passive"))
    )
    (net (code "132") (name "unconnected-(U1D-NC-PadA11)") (class "Default")
      (node (ref "U1") (pin "A11") (pinfunction "NC_A11") (pintype "passive"))
    )
    (net (code "133") (name "unconnected-(U1E-CLKIN-PadD7)") (class "Default")
      (node (ref "U1") (pin "D7") (pinfunction "CLKIN_D7") (pintype "passive"))
    )
    (net (code "134") (name "unconnected-(U1F-TCK-PadF6)") (class "Default")
      (node (ref "U1") (pin "F6") (pinfunction "TCK_F6") (pintype "passive"))
    )
    (net (code "135") (name "unconnected-(U1F-TDI-PadE7)") (class "Default")
      (node (ref "U1") (pin "E7") (pinfunction "TDI_E7") (pintype "passive"))
    )
    (net (code "136") (name "unconnected-(U1F-TDO-PadC10)") (class "Default")
      (node (ref "U1") (pin "C10") (pinfunction "TDO_C10") (pintype "passive"))
    )
    (net (code "137") (name "unconnected-(U1F-TMS-PadE8)") (class "Default")
      (node (ref "U1") (pin "E8") (pinfunction "TMS_E8") (pintype "passive"))
    )
    (net (code "138") (name "unconnected-(U1F-TRST_N-PadB11)") (class "Default")
      (node (ref "U1") (pin "B11") (pinfunction "TRST_N_B11") (pintype "passive"))
    )
    (net (code "139") (name "unconnected-(U1H-I2C-GPIO60_CHARGER-DETECT-PadD11)") (class "Default")
      (node (ref "U1") (pin "D11") (pinfunction "I2C-GPIO60_CHARGER-DETECT_D11") (pintype "passive+no_connect"))
    )
    (net (code "140") (name "unconnected-(U2-DU1-Pad1)") (class "Default")
      (node (ref "U2") (pin "1") (pinfunction "DU1_1") (pintype "passive"))
    )
    (net (code "141") (name "unconnected-(U2-DU2-Pad2)") (class "Default")
      (node (ref "U2") (pin "2") (pinfunction "DU2_2") (pintype "passive"))
    )
    (net (code "142") (name "unconnected-(U2-E2-Pad3)") (class "Default")
      (node (ref "U2") (pin "3") (pinfunction "E2_3") (pintype "passive"))
    )
    (net (code "143") (name "unconnected-(U2-~{WC}-Pad7)") (class "Default")
      (node (ref "U2") (pin "7") (pinfunction "~{WC}_7") (pintype "passive"))
    )
    (net (code "144") (name "unconnected-(U3-NC-Pad1)") (class "Default")
      (node (ref "U3") (pin "1") (pinfunction "NC_1") (pintype "passive"))
    )
    (net (code "145") (name "unconnected-(U3-NC-Pad2)") (class "Default")
      (node (ref "U3") (pin "2") (pinfunction "NC_2") (pintype "passive"))
    )
    (net (code "146") (name "unconnected-(U3-NC-Pad3)") (class "Default")
      (node (ref "U3") (pin "3") (pinfunction "NC_3") (pintype "passive"))
    )
    (net (code "147") (name "unconnected-(U3-NC-Pad7)") (class "Default")
      (node (ref "U3") (pin "7") (pinfunction "NC_7") (pintype "passive"))
    )
  )
)
